# PI_INTERFACE.net
KiCad netlist of a schematic drawn in Altium Designer
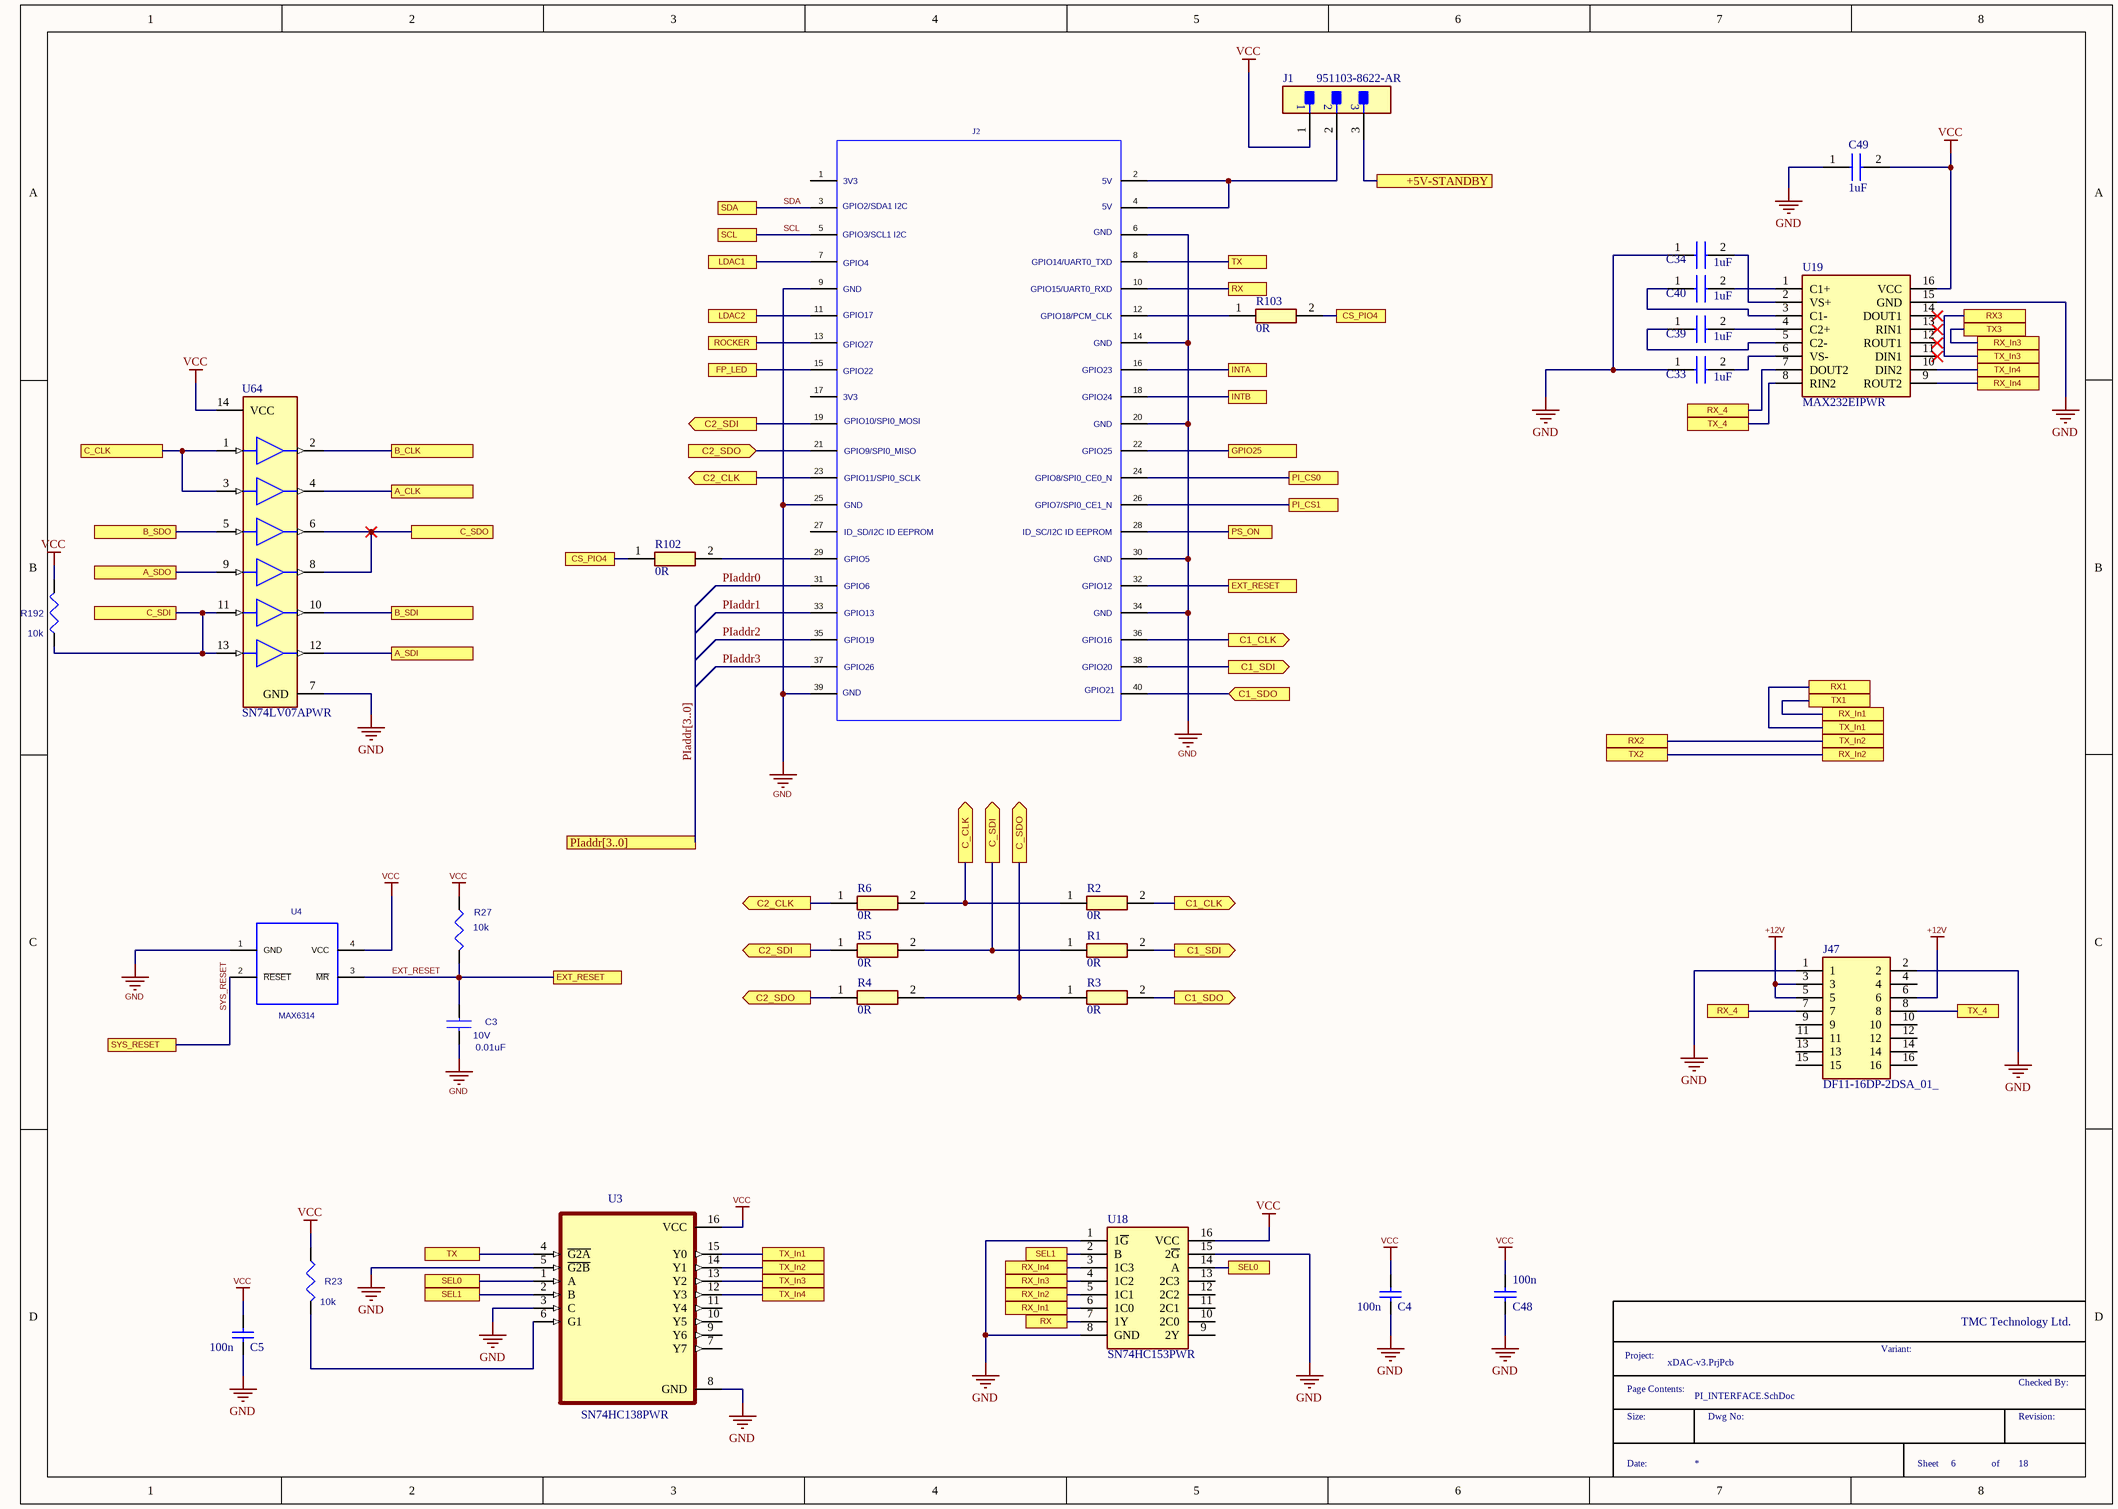
[diagram p0: PI_INTERFACE.SchDoc]

(export (version "E")
  (design (tool "Eeschema 10.0.6"))
  (components
    (comp (ref "C3")
      (value "0.01uF")
      (footprint "CC0603N")
      (description "CAP.,0.01uF,X5R,10V,10%,0603")
      (fields
        (field (name "MANUFACTURER") "AVX")
        (field (name "RATED_VOLTAGE") "10V")
        (field (name "TOLERANCE") "10%")
      )
      (libsource (lib "xDAC_Carrier") (part "CAP"))
    )
    (comp (ref "C4")
      (value "100n")
      (footprint "CAPC1608X90X35LL15T15")
      (description "Chip Capacitor, 100 nF, +/- 10%, 50 V, -55 to 125 degC, 0603 (1608 Metric), RoHS, Tape and Reel")
      (fields (field (name "TOLERANCE") "10%") (field (name "MANUFACTURER") "KEMET"))
      (libsource (lib "xDAC_Carrier") (part "CMP-1035-02592-3"))
    )
    (comp (ref "C5")
      (value "100n")
      (footprint "CAPC1608X90X35LL15T15")
      (description "Chip Capacitor, 100 nF, +/- 10%, 50 V, -55 to 125 degC, 0603 (1608 Metric), RoHS, Tape and Reel")
      (fields (field (name "TOLERANCE") "10%") (field (name "MANUFACTURER") "KEMET"))
      (libsource (lib "xDAC_Carrier") (part "CMP-1035-02592-3"))
    )
    (comp (ref "C33")
      (value "1uF")
      (footprint "CAPC1608X95N")
      (description "Capacitor")
      (fields
        (field (name "MANUFACTURER_PART_NUMBER") "CL10B105KB8NQNC")
        (field (name "MOUSER PART NUMBER") "187-CL10B105KB8NQNC")
      )
      (libsource (lib "xDAC_Carrier") (part "CL10B105KB8NQNC"))
    )
    (comp (ref "C34")
      (value "1uF")
      (footprint "CAPC1608X95N")
      (description "Capacitor")
      (fields
        (field (name "MANUFACTURER_PART_NUMBER") "CL10B105KB8NQNC")
        (field (name "MOUSER PART NUMBER") "187-CL10B105KB8NQNC")
      )
      (libsource (lib "xDAC_Carrier") (part "CL10B105KB8NQNC"))
    )
    (comp (ref "C39")
      (value "1uF")
      (footprint "CAPC1608X95N")
      (description "Capacitor")
      (fields
        (field (name "MANUFACTURER_PART_NUMBER") "CL10B105KB8NQNC")
        (field (name "MOUSER PART NUMBER") "187-CL10B105KB8NQNC")
      )
      (libsource (lib "xDAC_Carrier") (part "CL10B105KB8NQNC"))
    )
    (comp (ref "C40")
      (value "1uF")
      (footprint "CAPC1608X95N")
      (description "Capacitor")
      (fields
        (field (name "MANUFACTURER_PART_NUMBER") "CL10B105KB8NQNC")
        (field (name "MOUSER PART NUMBER") "187-CL10B105KB8NQNC")
      )
      (libsource (lib "xDAC_Carrier") (part "CL10B105KB8NQNC"))
    )
    (comp (ref "C48")
      (value "100n")
      (footprint "CAPC1608X90X35LL15T15")
      (description "Chip Capacitor, 100 nF, +/- 10%, 50 V, -55 to 125 degC, 0603 (1608 Metric), RoHS, Tape and Reel")
      (fields (field (name "TOLERANCE") "10%") (field (name "MANUFACTURER") "KEMET"))
      (libsource (lib "xDAC_Carrier") (part "CMP-1035-02592-3"))
    )
    (comp (ref "C49")
      (value "1uF")
      (footprint "CAPC1608X95N")
      (description "Capacitor")
      (fields
        (field (name "MANUFACTURER_PART_NUMBER") "CL10B105KB8NQNC")
        (field (name "MOUSER PART NUMBER") "187-CL10B105KB8NQNC")
      )
      (libsource (lib "xDAC_Carrier") (part "CL10B105KB8NQNC"))
    )
    (comp (ref "J1")
      (value "951103-8622-AR")
      (footprint "FP-951103-8622-AR-MFG")
      (description "CONN HEADER VERT 3POS 2MM")
      (fields
        (field (name "OCTOPART") "https://octopart.com/951103-8622-ar-3m-14400669")
        (field (name "MANUFACTURER") "3M")
      )
      (libsource (lib "xDAC_Carrier") (part "CMP-05379-000003-1"))
    )
    (comp (ref "J2")
      (value "RPI_PLUG")
      (footprint "HDRV40W64P254_2X20_5080X483X878P")
      (description "PCB Plug, Board-to-Board, 2.54 mm, 2 Rows, 40 Contacts, Through Hole Mount")
      (fields (field (name "MANUFACTURER") "Multicomp") (field (name "PART NO") "2214S-40SG-85"))
      (libsource (lib "xDAC_Carrier") (part "RPI_PLUG"))
    )
    (comp (ref "J47")
      (value "DF11-16DP-2DSA_01_")
      (footprint "DF1116DP2DSA01")
      (description "Connector")
      (fields
        (field (name "MANUFACTURER_PART_NUMBER") "DF11-16DP-2DSA(01)")
        (field (name "MOUSER PART NUMBER") "798-DF11-16DP-2DSA01")
      )
      (libsource (lib "xDAC_Carrier") (part "DF11-16DP-2DSA_01_"))
    )
    (comp (ref "R1")
      (value "0R")
      (footprint "RESC1608X55N")
      (description "Resistor")
      (fields
        (field (name "MANUFACTURER_PART_NUMBER") "RC0603FR-070RL")
        (field (name "MOUSER PART NUMBER") "603-RC0603FR-070RL")
      )
      (libsource (lib "Lyra_MB_PCB") (part "RC0603FR-070RL"))
    )
    (comp (ref "R2")
      (value "0R")
      (footprint "RESC1608X55N")
      (description "Resistor")
      (fields
        (field (name "MANUFACTURER_PART_NUMBER") "RC0603FR-070RL")
        (field (name "MOUSER PART NUMBER") "603-RC0603FR-070RL")
      )
      (libsource (lib "Lyra_MB_PCB") (part "RC0603FR-070RL"))
    )
    (comp (ref "R3")
      (value "0R")
      (footprint "RESC1608X55N")
      (description "Resistor")
      (fields
        (field (name "MANUFACTURER_PART_NUMBER") "RC0603FR-070RL")
        (field (name "MOUSER PART NUMBER") "603-RC0603FR-070RL")
      )
      (libsource (lib "Lyra_MB_PCB") (part "RC0603FR-070RL"))
    )
    (comp (ref "R4")
      (value "0R")
      (footprint "RESC1608X55N")
      (description "Resistor")
      (fields
        (field (name "MANUFACTURER_PART_NUMBER") "RC0603FR-070RL")
        (field (name "MOUSER PART NUMBER") "603-RC0603FR-070RL")
      )
      (libsource (lib "Lyra_MB_PCB") (part "RC0603FR-070RL"))
    )
    (comp (ref "R5")
      (value "0R")
      (footprint "RESC1608X55N")
      (description "Resistor")
      (fields
        (field (name "MANUFACTURER_PART_NUMBER") "RC0603FR-070RL")
        (field (name "MOUSER PART NUMBER") "603-RC0603FR-070RL")
      )
      (libsource (lib "Lyra_MB_PCB") (part "RC0603FR-070RL"))
    )
    (comp (ref "R6")
      (value "0R")
      (footprint "RESC1608X55N")
      (description "Resistor")
      (fields
        (field (name "MANUFACTURER_PART_NUMBER") "RC0603FR-070RL")
        (field (name "MOUSER PART NUMBER") "603-RC0603FR-070RL")
      )
      (libsource (lib "Lyra_MB_PCB") (part "RC0603FR-070RL"))
    )
    (comp (ref "R23")
      (value "10k")
      (footprint "CR0603N")
      (description "RES.,10k OHMS,1%,1/10W,0603")
      (fields (field (name "MANUFACTURER") "PANASONIC") (field (name "TOLERANCE") "1%"))
      (libsource (lib "xDAC_Carrier") (part "RES"))
    )
    (comp (ref "R27")
      (value "10k")
      (footprint "CR0603N")
      (description "RES.,10k OHMS,1%,1/10W,0603")
      (fields (field (name "MANUFACTURER") "PANASONIC") (field (name "TOLERANCE") "1%"))
      (libsource (lib "xDAC_Carrier") (part "RES"))
    )
    (comp (ref "R102")
      (value "0R")
      (footprint "RESC1608X55N")
      (description "Resistor")
      (fields
        (field (name "MANUFACTURER_PART_NUMBER") "RC0603FR-070RL")
        (field (name "MOUSER PART NUMBER") "603-RC0603FR-070RL")
      )
      (libsource (lib "") (part "RC0603FR-070RL_1"))
    )
    (comp (ref "R103")
      (value "0R")
      (footprint "RESC1608X55N")
      (description "Resistor")
      (fields
        (field (name "MANUFACTURER_PART_NUMBER") "RC0603FR-070RL")
        (field (name "MOUSER PART NUMBER") "603-RC0603FR-070RL")
      )
      (libsource (lib "Pilot") (part "RC0603FR-070RL"))
    )
    (comp (ref "R192")
      (value "10k")
      (footprint "CR0603N")
      (description "RES.,10k OHMS,1%,1/10W,0603")
      (fields (field (name "MANUFACTURER") "PANASONIC") (field (name "TOLERANCE") "1%"))
      (libsource (lib "xDAC_Carrier") (part "RES"))
    )
    (comp (ref "U3")
      (value "SN74HC138PWR")
      (footprint "SOP65P640X120-16N")
      (description "3-Line To 8-Line Decoders/Demultiplexers 16-TSSOP -40 to 85")
      (fields (field (name "MF") "Texas Instruments"))
      (libsource (lib "xDAC_Carrier") (part "SN74HC138PWR"))
    )
    (comp (ref "U4")
      (value "MAX6314")
      (footprint "SOT190P230X110-4N")
      (description "IC SUPERVISOR 1 CHANNEL SOT143-4")
      (fields (field (name "MANUFACTURER") "Maxim") (field (name "PART NO") "MAX6314US46D3+T"))
      (libsource (lib "xDAC_Carrier") (part "MAX6314"))
    )
    (comp (ref "U18")
      (value "SN74HC153PWR")
      (footprint "SOP65P640X120-16N")
      (description "Integrated Circuit")
      (fields (field (name "MOUSER PART NUMBER") "595-SN74HC153PWR"))
      (libsource (lib "xDAC_Carrier") (part "SN74HC153PWR"))
    )
    (comp (ref "U19")
      (value "MAX232EIPWR")
      (footprint "SOP65P640X120-16N")
      (description "Integrated Circuit")
      (fields (field (name "MOUSER PART NUMBER") "595-MAX232EIPWR"))
      (libsource (lib "xDAC_Carrier") (part "MAX232EIPWR"))
    )
    (comp (ref "U64")
      (value "SN74LV07APWR")
      (footprint "FP-PW0014A-IPC_B")
      (description "IC BUF NON-INVERT 5.5V 14TSSOP")
      (libsource (lib "Altium Content Vault") (part "8277e3df8f81b2f99000276f6310c4d"))
    )
  )
  (nets
    (net (code "1") (name "+12V") (class "Default")
      (node (ref "J47") (pin "3") (pinfunction "3_3") (pintype "passive"))
      (node (ref "J47") (pin "5") (pinfunction "5_5") (pintype "passive"))
      (node (ref "J47") (pin "6") (pinfunction "6_6") (pintype "passive"))
    )
    (net (code "2") (name "/+5V-STANDBY") (class "Default")
      (node (ref "J1") (pin "3") (pinfunction "3_3") (pintype "passive"))
    )
    (net (code "3") (name "/A_CLK") (class "Default")
      (node (ref "U64") (pin "4") (pinfunction "2Y_4") (pintype "output"))
    )
    (net (code "4") (name "/A_SDI") (class "Default")
      (node (ref "U64") (pin "12") (pinfunction "6Y_12") (pintype "output"))
    )
    (net (code "5") (name "/A_SDO") (class "Default")
      (node (ref "U64") (pin "9") (pinfunction "4A_9") (pintype "input"))
    )
    (net (code "6") (name "/B_CLK") (class "Default")
      (node (ref "U64") (pin "2") (pinfunction "1Y_2") (pintype "output"))
    )
    (net (code "7") (name "/B_SDI") (class "Default")
      (node (ref "U64") (pin "10") (pinfunction "5Y_10") (pintype "output"))
    )
    (net (code "8") (name "/B_SDO") (class "Default")
      (node (ref "U64") (pin "5") (pinfunction "3A_5") (pintype "input"))
    )
    (net (code "9") (name "/C1_CLK") (class "Default")
      (node (ref "J2") (pin "36") (pinfunction "36_36") (pintype "passive"))
      (node (ref "R2") (pin "2") (pinfunction "2_2") (pintype "passive"))
    )
    (net (code "10") (name "/C1_SDI") (class "Default")
      (node (ref "J2") (pin "38") (pinfunction "38_38") (pintype "passive"))
      (node (ref "R1") (pin "2") (pinfunction "2_2") (pintype "passive"))
    )
    (net (code "11") (name "/C1_SDO") (class "Default")
      (node (ref "J2") (pin "40") (pinfunction "40_40") (pintype "passive"))
      (node (ref "R3") (pin "2") (pinfunction "2_2") (pintype "passive"))
    )
    (net (code "12") (name "/C2_CLK") (class "Default")
      (node (ref "J2") (pin "23") (pinfunction "23_23") (pintype "passive"))
      (node (ref "R6") (pin "1") (pinfunction "1_1") (pintype "passive"))
    )
    (net (code "13") (name "/C2_SDI") (class "Default")
      (node (ref "J2") (pin "19") (pinfunction "19_19") (pintype "passive"))
      (node (ref "R5") (pin "1") (pinfunction "1_1") (pintype "passive"))
    )
    (net (code "14") (name "/C2_SDO") (class "Default")
      (node (ref "J2") (pin "21") (pinfunction "21_21") (pintype "passive"))
      (node (ref "R4") (pin "1") (pinfunction "1_1") (pintype "passive"))
    )
    (net (code "15") (name "/CS_PIO4") (class "Default")
      (node (ref "R102") (pin "1") (pinfunction "1_1") (pintype "passive"))
      (node (ref "R103") (pin "2") (pinfunction "2_2") (pintype "passive"))
    )
    (net (code "16") (name "/C_CLK") (class "Default")
      (node (ref "R2") (pin "1") (pinfunction "1_1") (pintype "passive"))
      (node (ref "R6") (pin "2") (pinfunction "2_2") (pintype "passive"))
      (node (ref "U64") (pin "1") (pinfunction "1A_1") (pintype "input"))
      (node (ref "U64") (pin "3") (pinfunction "2A_3") (pintype "input"))
    )
    (net (code "17") (name "/C_SDI") (class "Default")
      (node (ref "R1") (pin "1") (pinfunction "1_1") (pintype "passive"))
      (node (ref "R192") (pin "2") (pinfunction "2_2") (pintype "passive"))
      (node (ref "R5") (pin "2") (pinfunction "2_2") (pintype "passive"))
      (node (ref "U64") (pin "11") (pinfunction "5A_11") (pintype "input"))
      (node (ref "U64") (pin "13") (pinfunction "6A_13") (pintype "input"))
    )
    (net (code "18") (name "/C_SDO") (class "Default")
      (node (ref "R3") (pin "1") (pinfunction "1_1") (pintype "passive"))
      (node (ref "R4") (pin "2") (pinfunction "2_2") (pintype "passive"))
      (node (ref "U64") (pin "6") (pinfunction "3Y_6") (pintype "output"))
      (node (ref "U64") (pin "8") (pinfunction "4Y_8") (pintype "output"))
    )
    (net (code "19") (name "/EXT_RESET") (class "Default")
      (node (ref "C3") (pin "1") (pinfunction "1_1") (pintype "passive"))
      (node (ref "J2") (pin "32") (pinfunction "32_32") (pintype "passive"))
      (node (ref "R27") (pin "2") (pinfunction "2_2") (pintype "passive"))
      (node (ref "U4") (pin "3") (pinfunction "MR_3") (pintype "passive"))
    )
    (net (code "20") (name "/FP_LED") (class "Default")
      (node (ref "J2") (pin "15") (pinfunction "15_15") (pintype "passive"))
    )
    (net (code "21") (name "/GPIO25") (class "Default")
      (node (ref "J2") (pin "22") (pinfunction "22_22") (pintype "passive"))
    )
    (net (code "22") (name "/INTA") (class "Default")
      (node (ref "J2") (pin "16") (pinfunction "16_16") (pintype "passive"))
    )
    (net (code "23") (name "/INTB") (class "Default")
      (node (ref "J2") (pin "18") (pinfunction "18_18") (pintype "passive"))
    )
    (net (code "24") (name "/LDAC1") (class "Default")
      (node (ref "J2") (pin "7") (pinfunction "7_7") (pintype "passive"))
    )
    (net (code "25") (name "/LDAC2") (class "Default")
      (node (ref "J2") (pin "11") (pinfunction "11_11") (pintype "passive"))
    )
    (net (code "26") (name "/PI_CS0") (class "Default")
      (node (ref "J2") (pin "24") (pinfunction "24_24") (pintype "passive"))
    )
    (net (code "27") (name "/PI_CS1") (class "Default")
      (node (ref "J2") (pin "26") (pinfunction "26_26") (pintype "passive"))
    )
    (net (code "28") (name "/PIaddr0") (class "Default")
      (node (ref "J2") (pin "31") (pinfunction "31_31") (pintype "passive"))
    )
    (net (code "29") (name "/PIaddr1") (class "Default")
      (node (ref "J2") (pin "33") (pinfunction "33_33") (pintype "passive"))
    )
    (net (code "30") (name "/PIaddr2") (class "Default")
      (node (ref "J2") (pin "35") (pinfunction "35_35") (pintype "passive"))
    )
    (net (code "31") (name "/PIaddr3") (class "Default")
      (node (ref "J2") (pin "37") (pinfunction "37_37") (pintype "passive"))
    )
    (net (code "33") (name "/PS_ON") (class "Default")
      (node (ref "J2") (pin "28") (pinfunction "28_28") (pintype "passive"))
    )
    (net (code "34") (name "/ROCKER") (class "Default")
      (node (ref "J2") (pin "13") (pinfunction "13_13") (pintype "passive"))
    )
    (net (code "35") (name "/RX") (class "Default")
      (node (ref "J2") (pin "10") (pinfunction "10_10") (pintype "passive"))
      (node (ref "U18") (pin "7") (pinfunction "1Y_7") (pintype "passive"))
    )
    (net (code "36") (name "/RX1") (class "Default")
      (node (ref "U3") (pin "15") (pinfunction "Y0_15") (pintype "output"))
    )
    (net (code "37") (name "/RX2") (class "Default")
      (node (ref "U3") (pin "14") (pinfunction "Y1_14") (pintype "output"))
    )
    (net (code "38") (name "/RX3") (class "Default")
      (node (ref "U3") (pin "13") (pinfunction "Y2_13") (pintype "output"))
    )
    (net (code "39") (name "/RX_4") (class "Default")
      (node (ref "J47") (pin "7") (pinfunction "7_7") (pintype "passive"))
      (node (ref "U19") (pin "7") (pinfunction "DOUT2_7") (pintype "passive"))
    )
    (net (code "40") (name "/RX_In1") (class "Default")
      (node (ref "U18") (pin "6") (pinfunction "1C0_6") (pintype "passive"))
    )
    (net (code "41") (name "/RX_In2") (class "Default")
      (node (ref "U18") (pin "5") (pinfunction "1C1_5") (pintype "passive"))
    )
    (net (code "42") (name "/RX_In3") (class "Default")
      (node (ref "U18") (pin "4") (pinfunction "1C2_4") (pintype "passive"))
    )
    (net (code "43") (name "/RX_In4") (class "Default")
      (node (ref "U18") (pin "3") (pinfunction "1C3_3") (pintype "passive"))
      (node (ref "U19") (pin "9") (pinfunction "ROUT2_9") (pintype "passive"))
    )
    (net (code "44") (name "/SCL") (class "Default")
      (node (ref "J2") (pin "5") (pinfunction "5_5") (pintype "passive"))
    )
    (net (code "45") (name "/SDA") (class "Default")
      (node (ref "J2") (pin "3") (pinfunction "3_3") (pintype "passive"))
    )
    (net (code "46") (name "/SEL0") (class "Default")
      (node (ref "U18") (pin "14") (pinfunction "A_14") (pintype "passive"))
      (node (ref "U3") (pin "1") (pinfunction "A_1") (pintype "input"))
    )
    (net (code "47") (name "/SEL1") (class "Default")
      (node (ref "U18") (pin "2") (pinfunction "B_2") (pintype "passive"))
      (node (ref "U3") (pin "2") (pinfunction "B_2") (pintype "input"))
    )
    (net (code "48") (name "/SYS_RESET") (class "Default")
      (node (ref "U4") (pin "2") (pinfunction "RESET_2") (pintype "passive"))
    )
    (net (code "49") (name "/TX") (class "Default")
      (node (ref "J2") (pin "8") (pinfunction "8_8") (pintype "passive"))
      (node (ref "U3") (pin "4") (pinfunction "~{G2A}_4") (pintype "input"))
    )
    (net (code "50") (name "/TX_4") (class "Default")
      (node (ref "J47") (pin "8") (pinfunction "8_8") (pintype "passive"))
      (node (ref "U19") (pin "8") (pinfunction "RIN2_8") (pintype "passive"))
    )
    (net (code "51") (name "/TX_In4") (class "Default")
      (node (ref "U19") (pin "10") (pinfunction "DIN2_10") (pintype "passive"))
      (node (ref "U3") (pin "12") (pinfunction "Y3_12") (pintype "output"))
    )
    (net (code "52") (name "GND") (class "Default")
      (node (ref "C3") (pin "2") (pinfunction "2_2") (pintype "passive"))
      (node (ref "C33") (pin "1") (pinfunction "1_1") (pintype "passive"))
      (node (ref "C34") (pin "1") (pinfunction "1_1") (pintype "passive"))
      (node (ref "C4") (pin "2") (pinfunction "2_2") (pintype "passive"))
      (node (ref "C48") (pin "2") (pinfunction "2_2") (pintype "passive"))
      (node (ref "C49") (pin "1") (pinfunction "1_1") (pintype "passive"))
      (node (ref "C5") (pin "2") (pinfunction "2_2") (pintype "passive"))
      (node (ref "J2") (pin "14") (pinfunction "14_14") (pintype "passive"))
      (node (ref "J2") (pin "20") (pinfunction "20_20") (pintype "passive"))
      (node (ref "J2") (pin "25") (pinfunction "25_25") (pintype "passive"))
      (node (ref "J2") (pin "30") (pinfunction "30_30") (pintype "passive"))
      (node (ref "J2") (pin "34") (pinfunction "34_34") (pintype "passive"))
      (node (ref "J2") (pin "39") (pinfunction "39_39") (pintype "passive"))
      (node (ref "J2") (pin "6") (pinfunction "6_6") (pintype "passive"))
      (node (ref "J2") (pin "9") (pinfunction "9_9") (pintype "passive"))
      (node (ref "J47") (pin "1") (pinfunction "1_1") (pintype "passive"))
      (node (ref "J47") (pin "2") (pinfunction "2_2") (pintype "passive"))
      (node (ref "U18") (pin "1") (pinfunction "1~{G}_1") (pintype "passive"))
      (node (ref "U18") (pin "15") (pinfunction "2~{G}_15") (pintype "passive"))
      (node (ref "U18") (pin "8") (pinfunction "GND_8") (pintype "passive"))
      (node (ref "U19") (pin "15") (pinfunction "GND_15") (pintype "passive"))
      (node (ref "U3") (pin "3") (pinfunction "C_3") (pintype "input"))
      (node (ref "U3") (pin "5") (pinfunction "~{G2B}_5") (pintype "input"))
      (node (ref "U3") (pin "8") (pinfunction "GND_8") (pintype "power_in"))
      (node (ref "U4") (pin "1") (pinfunction "GND_1") (pintype "passive"))
      (node (ref "U64") (pin "7") (pinfunction "GND_7") (pintype "power_in"))
    )
    (net (code "53") (name "Net-(J1-Pad2)") (class "Default")
      (node (ref "J1") (pin "2") (pinfunction "2_2") (pintype "passive"))
      (node (ref "J2") (pin "2") (pinfunction "2_2") (pintype "passive"))
      (node (ref "J2") (pin "4") (pinfunction "4_4") (pintype "passive"))
    )
    (net (code "54") (name "Net-(J2-Pad12)") (class "Default")
      (node (ref "J2") (pin "12") (pinfunction "12_12") (pintype "passive"))
      (node (ref "R103") (pin "1") (pinfunction "1_1") (pintype "passive"))
    )
    (net (code "55") (name "Net-(J2-Pad29)") (class "Default")
      (node (ref "J2") (pin "29") (pinfunction "29_29") (pintype "passive"))
      (node (ref "R102") (pin "2") (pinfunction "2_2") (pintype "passive"))
    )
    (net (code "56") (name "Net-(U3-G1)") (class "Default")
      (node (ref "R23") (pin "2") (pinfunction "2_2") (pintype "passive"))
      (node (ref "U3") (pin "6") (pinfunction "G1_6") (pintype "input"))
    )
    (net (code "57") (name "Net-(U19-C1+)") (class "Default")
      (node (ref "C40") (pin "2") (pinfunction "2_2") (pintype "passive"))
      (node (ref "U19") (pin "1") (pinfunction "C1+_1") (pintype "passive"))
    )
    (net (code "58") (name "Net-(U19-C1-)") (class "Default")
      (node (ref "C40") (pin "1") (pinfunction "1_1") (pintype "passive"))
      (node (ref "U19") (pin "3") (pinfunction "C1-_3") (pintype "passive"))
    )
    (net (code "59") (name "Net-(U19-C2+)") (class "Default")
      (node (ref "C39") (pin "2") (pinfunction "2_2") (pintype "passive"))
      (node (ref "U19") (pin "4") (pinfunction "C2+_4") (pintype "passive"))
    )
    (net (code "60") (name "Net-(U19-C2-)") (class "Default")
      (node (ref "C39") (pin "1") (pinfunction "1_1") (pintype "passive"))
      (node (ref "U19") (pin "5") (pinfunction "C2-_5") (pintype "passive"))
    )
    (net (code "61") (name "Net-(U19-VS+)") (class "Default")
      (node (ref "C34") (pin "2") (pinfunction "2_2") (pintype "passive"))
      (node (ref "U19") (pin "2") (pinfunction "VS+_2") (pintype "passive"))
    )
    (net (code "62") (name "Net-(U19-VS-)") (class "Default")
      (node (ref "C33") (pin "2") (pinfunction "2_2") (pintype "passive"))
      (node (ref "U19") (pin "6") (pinfunction "VS-_6") (pintype "passive"))
    )
    (net (code "63") (name "VCC") (class "Default")
      (node (ref "C4") (pin "1") (pinfunction "1_1") (pintype "passive"))
      (node (ref "C48") (pin "1") (pinfunction "1_1") (pintype "passive"))
      (node (ref "C49") (pin "2") (pinfunction "2_2") (pintype "passive"))
      (node (ref "C5") (pin "1") (pinfunction "1_1") (pintype "passive"))
      (node (ref "J1") (pin "1") (pinfunction "1_1") (pintype "passive"))
      (node (ref "R192") (pin "1") (pinfunction "1_1") (pintype "passive"))
      (node (ref "R23") (pin "1") (pinfunction "1_1") (pintype "passive"))
      (node (ref "R27") (pin "1") (pinfunction "1_1") (pintype "passive"))
      (node (ref "U18") (pin "16") (pinfunction "VCC_16") (pintype "passive"))
      (node (ref "U19") (pin "16") (pinfunction "VCC_16") (pintype "passive"))
      (node (ref "U3") (pin "16") (pinfunction "VCC_16") (pintype "power_in"))
      (node (ref "U4") (pin "4") (pinfunction "VCC_4") (pintype "passive"))
      (node (ref "U64") (pin "14") (pinfunction "VCC_14") (pintype "power_in"))
    )
    (net (code "64") (name "unconnected-(J2-Pad1)") (class "Default")
      (node (ref "J2") (pin "1") (pinfunction "1_1") (pintype "passive"))
    )
    (net (code "65") (name "unconnected-(J2-Pad17)") (class "Default")
      (node (ref "J2") (pin "17") (pinfunction "17_17") (pintype "passive"))
    )
    (net (code "66") (name "unconnected-(J2-Pad27)") (class "Default")
      (node (ref "J2") (pin "27") (pinfunction "27_27") (pintype "passive"))
    )
    (net (code "67") (name "unconnected-(J47-Pad4)") (class "Default")
      (node (ref "J47") (pin "4") (pinfunction "4_4") (pintype "passive"))
    )
    (net (code "68") (name "unconnected-(J47-Pad9)") (class "Default")
      (node (ref "J47") (pin "9") (pinfunction "9_9") (pintype "passive"))
    )
    (net (code "69") (name "unconnected-(J47-Pad10)") (class "Default")
      (node (ref "J47") (pin "10") (pinfunction "10_10") (pintype "passive"))
    )
    (net (code "70") (name "unconnected-(J47-Pad11)") (class "Default")
      (node (ref "J47") (pin "11") (pinfunction "11_11") (pintype "passive"))
    )
    (net (code "71") (name "unconnected-(J47-Pad12)") (class "Default")
      (node (ref "J47") (pin "12") (pinfunction "12_12") (pintype "passive"))
    )
    (net (code "72") (name "unconnected-(J47-Pad13)") (class "Default")
      (node (ref "J47") (pin "13") (pinfunction "13_13") (pintype "passive"))
    )
    (net (code "73") (name "unconnected-(J47-Pad14)") (class "Default")
      (node (ref "J47") (pin "14") (pinfunction "14_14") (pintype "passive"))
    )
    (net (code "74") (name "unconnected-(J47-Pad15)") (class "Default")
      (node (ref "J47") (pin "15") (pinfunction "15_15") (pintype "passive"))
    )
    (net (code "75") (name "unconnected-(J47-Pad16)") (class "Default")
      (node (ref "J47") (pin "16") (pinfunction "16_16") (pintype "passive"))
    )
    (net (code "76") (name "unconnected-(U3-Y4-Pad11)") (class "Default")
      (node (ref "U3") (pin "11") (pinfunction "Y4_11") (pintype "output"))
    )
    (net (code "77") (name "unconnected-(U3-Y5-Pad10)") (class "Default")
      (node (ref "U3") (pin "10") (pinfunction "Y5_10") (pintype "output"))
    )
    (net (code "78") (name "unconnected-(U3-Y6-Pad9)") (class "Default")
      (node (ref "U3") (pin "9") (pinfunction "Y6_9") (pintype "output"))
    )
    (net (code "79") (name "unconnected-(U3-Y7-Pad7)") (class "Default")
      (node (ref "U3") (pin "7") (pinfunction "Y7_7") (pintype "output"))
    )
    (net (code "80") (name "unconnected-(U18-2C0-Pad10)") (class "Default")
      (node (ref "U18") (pin "10") (pinfunction "2C0_10") (pintype "passive"))
    )
    (net (code "81") (name "unconnected-(U18-2C1-Pad11)") (class "Default")
      (node (ref "U18") (pin "11") (pinfunction "2C1_11") (pintype "passive"))
    )
    (net (code "82") (name "unconnected-(U18-2C2-Pad12)") (class "Default")
      (node (ref "U18") (pin "12") (pinfunction "2C2_12") (pintype "passive"))
    )
    (net (code "83") (name "unconnected-(U18-2C3-Pad13)") (class "Default")
      (node (ref "U18") (pin "13") (pinfunction "2C3_13") (pintype "passive"))
    )
    (net (code "84") (name "unconnected-(U18-2Y-Pad9)") (class "Default")
      (node (ref "U18") (pin "9") (pinfunction "2Y_9") (pintype "passive"))
    )
    (net (code "85") (name "unconnected-(U19-DIN1-Pad11)") (class "Default")
      (node (ref "U19") (pin "11") (pinfunction "DIN1_11") (pintype "passive+no_connect"))
    )
    (net (code "86") (name "unconnected-(U19-DOUT1-Pad14)") (class "Default")
      (node (ref "U19") (pin "14") (pinfunction "DOUT1_14") (pintype "passive+no_connect"))
    )
    (net (code "87") (name "unconnected-(U19-RIN1-Pad13)") (class "Default")
      (node (ref "U19") (pin "13") (pinfunction "RIN1_13") (pintype "passive+no_connect"))
    )
    (net (code "88") (name "unconnected-(U19-ROUT1-Pad12)") (class "Default")
      (node (ref "U19") (pin "12") (pinfunction "ROUT1_12") (pintype "passive+no_connect"))
    )
  )
)
